# r2.net
KiCad netlist of a schematic drawn in EasyEDA
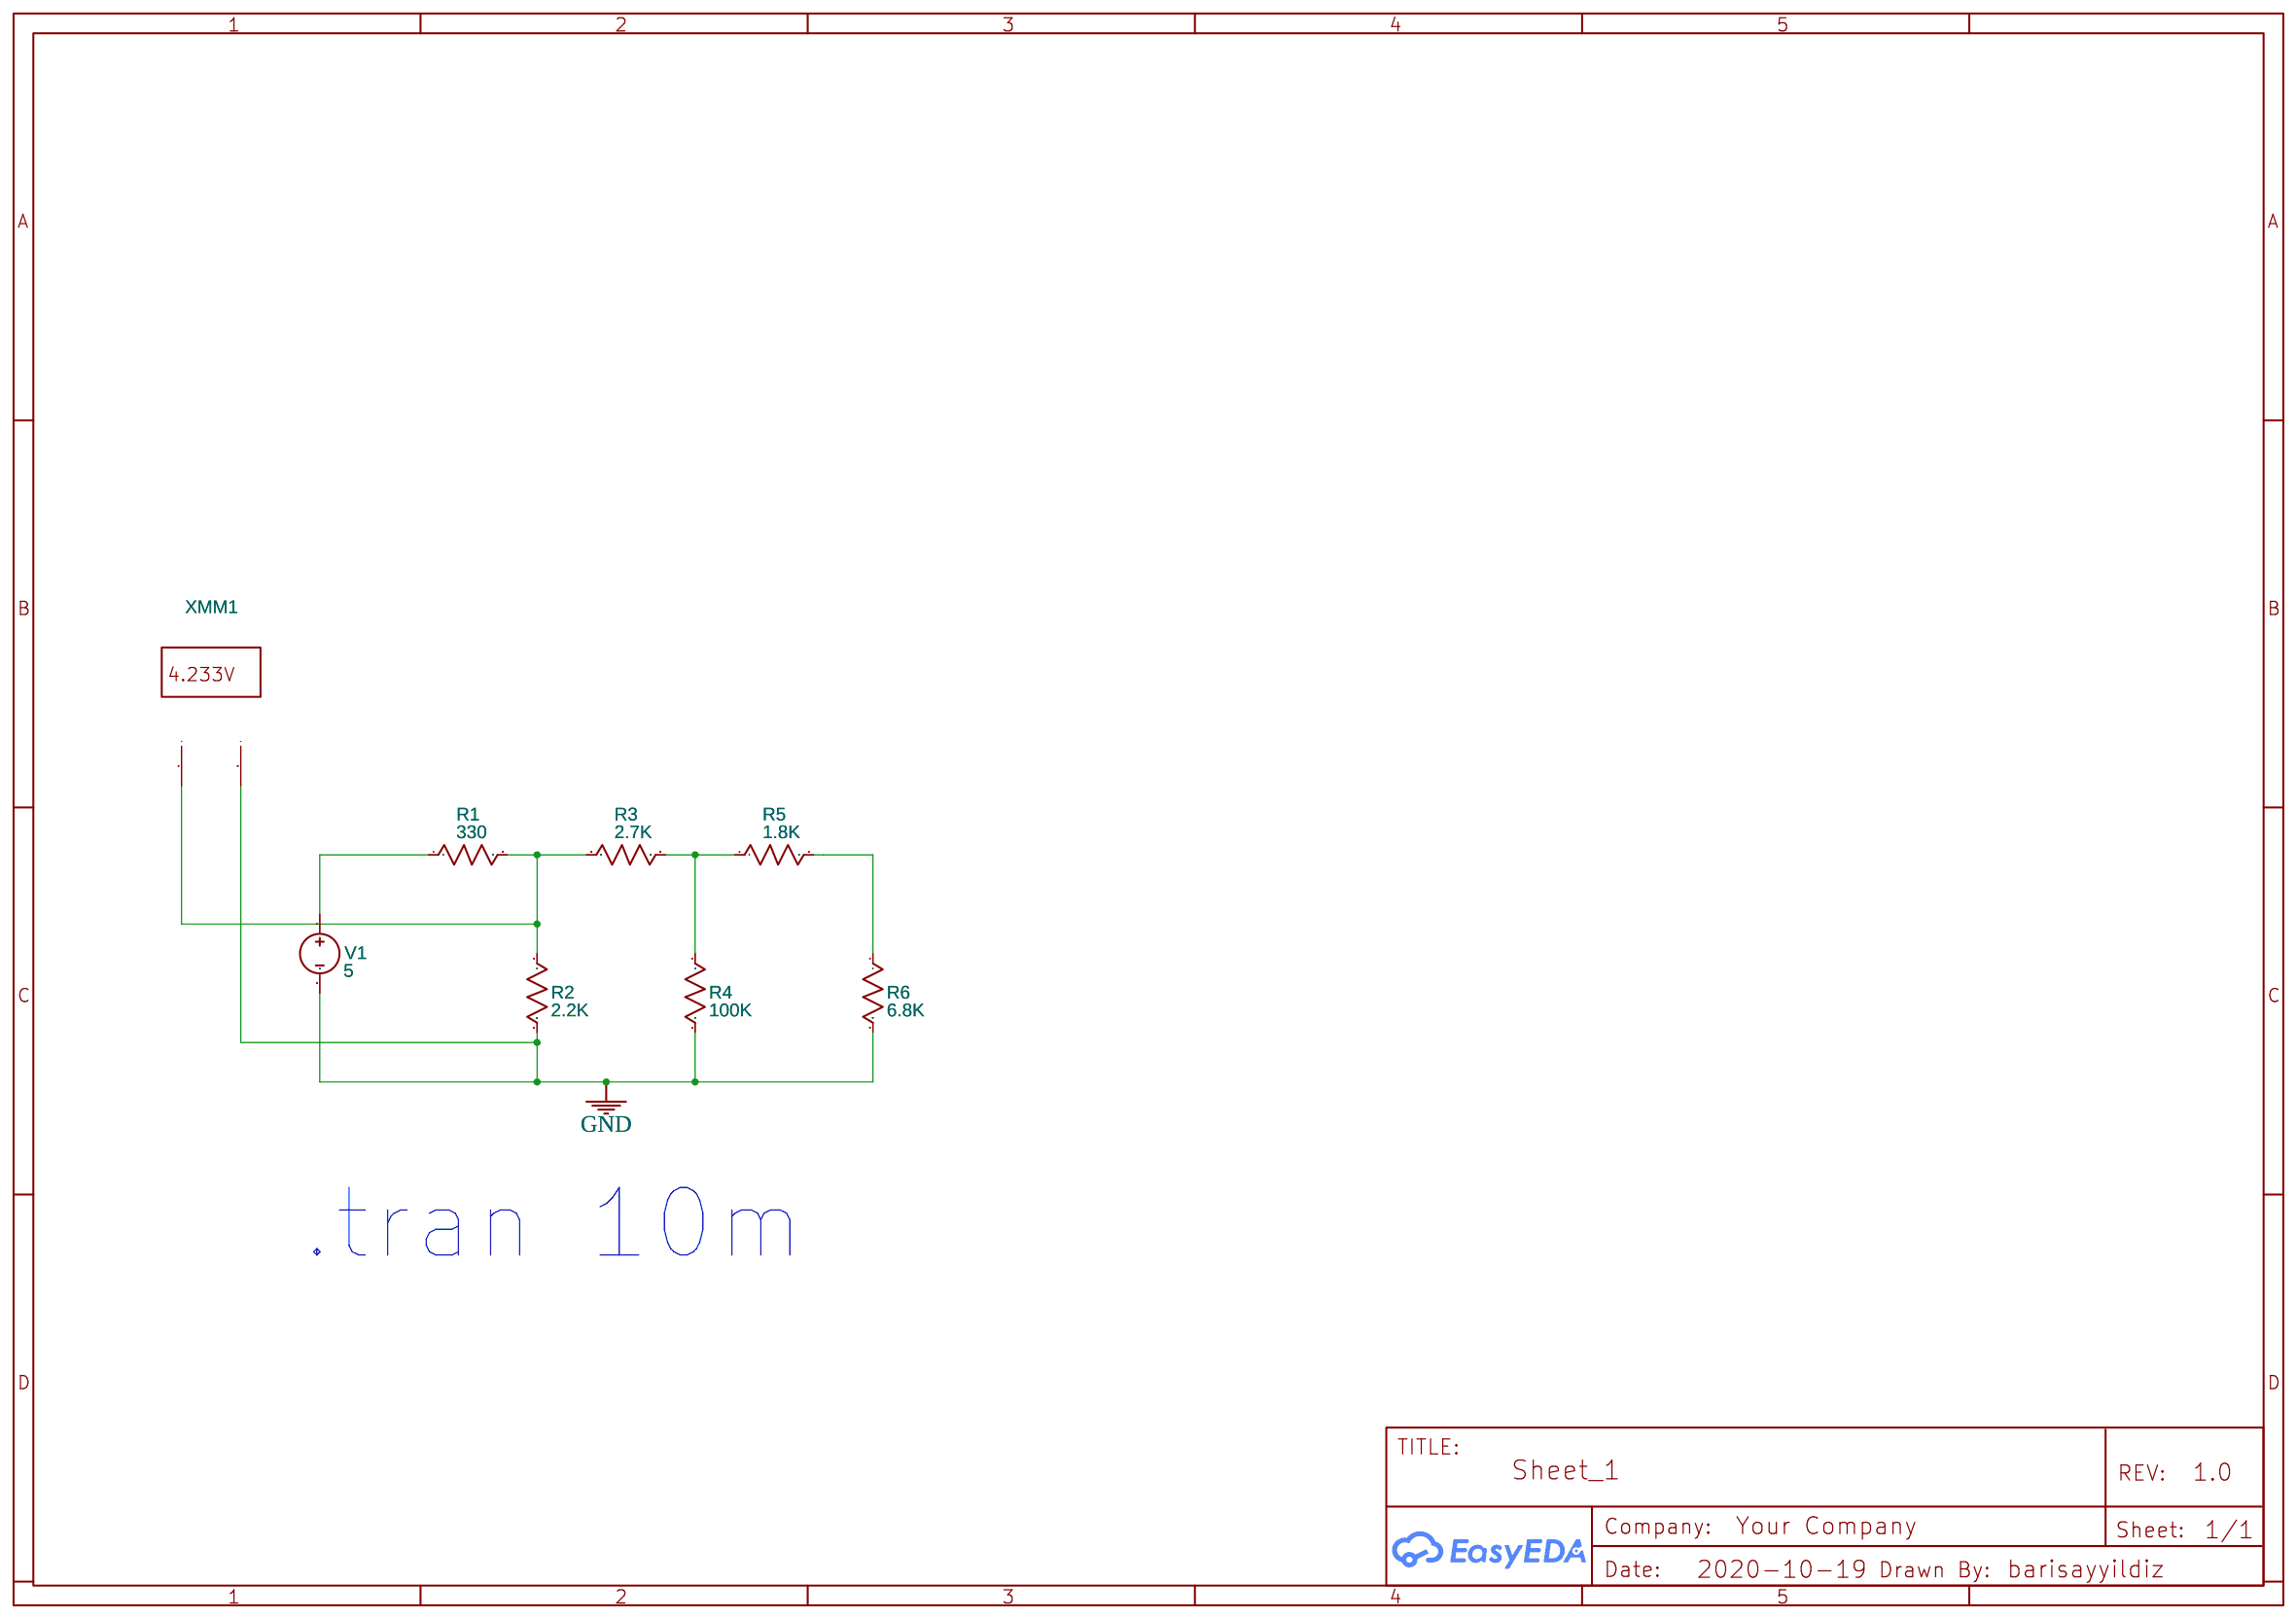
[diagram p0: schematic sheet]

(export (version "E")
  (design (tool "Eeschema 10.0.6"))
  (components
    (comp (ref "R1") (value "330") (libsource (lib "") (part "Resistor_US")))
    (comp (ref "R2") (value "2.2K") (libsource (lib "") (part "Resistor_US_1")))
    (comp (ref "R3") (value "2.7K") (libsource (lib "") (part "Resistor_US")))
    (comp (ref "R4") (value "100K") (libsource (lib "") (part "Resistor_US_1")))
    (comp (ref "R5") (value "1.8K") (libsource (lib "") (part "Resistor_US")))
    (comp (ref "R6") (value "6.8K") (libsource (lib "") (part "Resistor_US_1")))
    (comp (ref "V1") (value "5") (libsource (lib "") (part "VDC")))
    (comp (ref "XMM1") (value "Multimeter") (libsource (lib "") (part "MULTIMETER")))
  )
  (nets
    (net (code "1") (name "GND") (class "Default")
      (node (ref "R2") (pin "2") (pinfunction "2_2") (pintype "unspecified"))
      (node (ref "R4") (pin "2") (pinfunction "2_2") (pintype "unspecified"))
      (node (ref "R6") (pin "2") (pinfunction "2_2") (pintype "unspecified"))
      (node (ref "V1") (pin "2") (pinfunction "2_2") (pintype "unspecified"))
      (node (ref "XMM1") (pin "2") (pinfunction "I_2") (pintype "unspecified"))
    )
    (net (code "2") (name "Net-(R1-Pad1)") (class "Default")
      (node (ref "R1") (pin "1") (pinfunction "1_1") (pintype "unspecified"))
      (node (ref "V1") (pin "1") (pinfunction "1_1") (pintype "unspecified"))
    )
    (net (code "3") (name "Net-(R3-Pad2)") (class "Default")
      (node (ref "R3") (pin "2") (pinfunction "2_2") (pintype "unspecified"))
      (node (ref "R4") (pin "1") (pinfunction "1_1") (pintype "unspecified"))
      (node (ref "R5") (pin "1") (pinfunction "1_1") (pintype "unspecified"))
    )
    (net (code "4") (name "Net-(R5-Pad2)") (class "Default")
      (node (ref "R5") (pin "2") (pinfunction "2_2") (pintype "unspecified"))
      (node (ref "R6") (pin "1") (pinfunction "1_1") (pintype "unspecified"))
    )
    (net (code "5") (name "Net-(XMM1-+)") (class "Default")
      (node (ref "R1") (pin "2") (pinfunction "2_2") (pintype "unspecified"))
      (node (ref "R2") (pin "1") (pinfunction "1_1") (pintype "unspecified"))
      (node (ref "R3") (pin "1") (pinfunction "1_1") (pintype "unspecified"))
      (node (ref "XMM1") (pin "1") (pinfunction "+_1") (pintype "unspecified"))
    )
  )
)
